# untitled.net
KiCad netlist of a schematic drawn in EAGLE
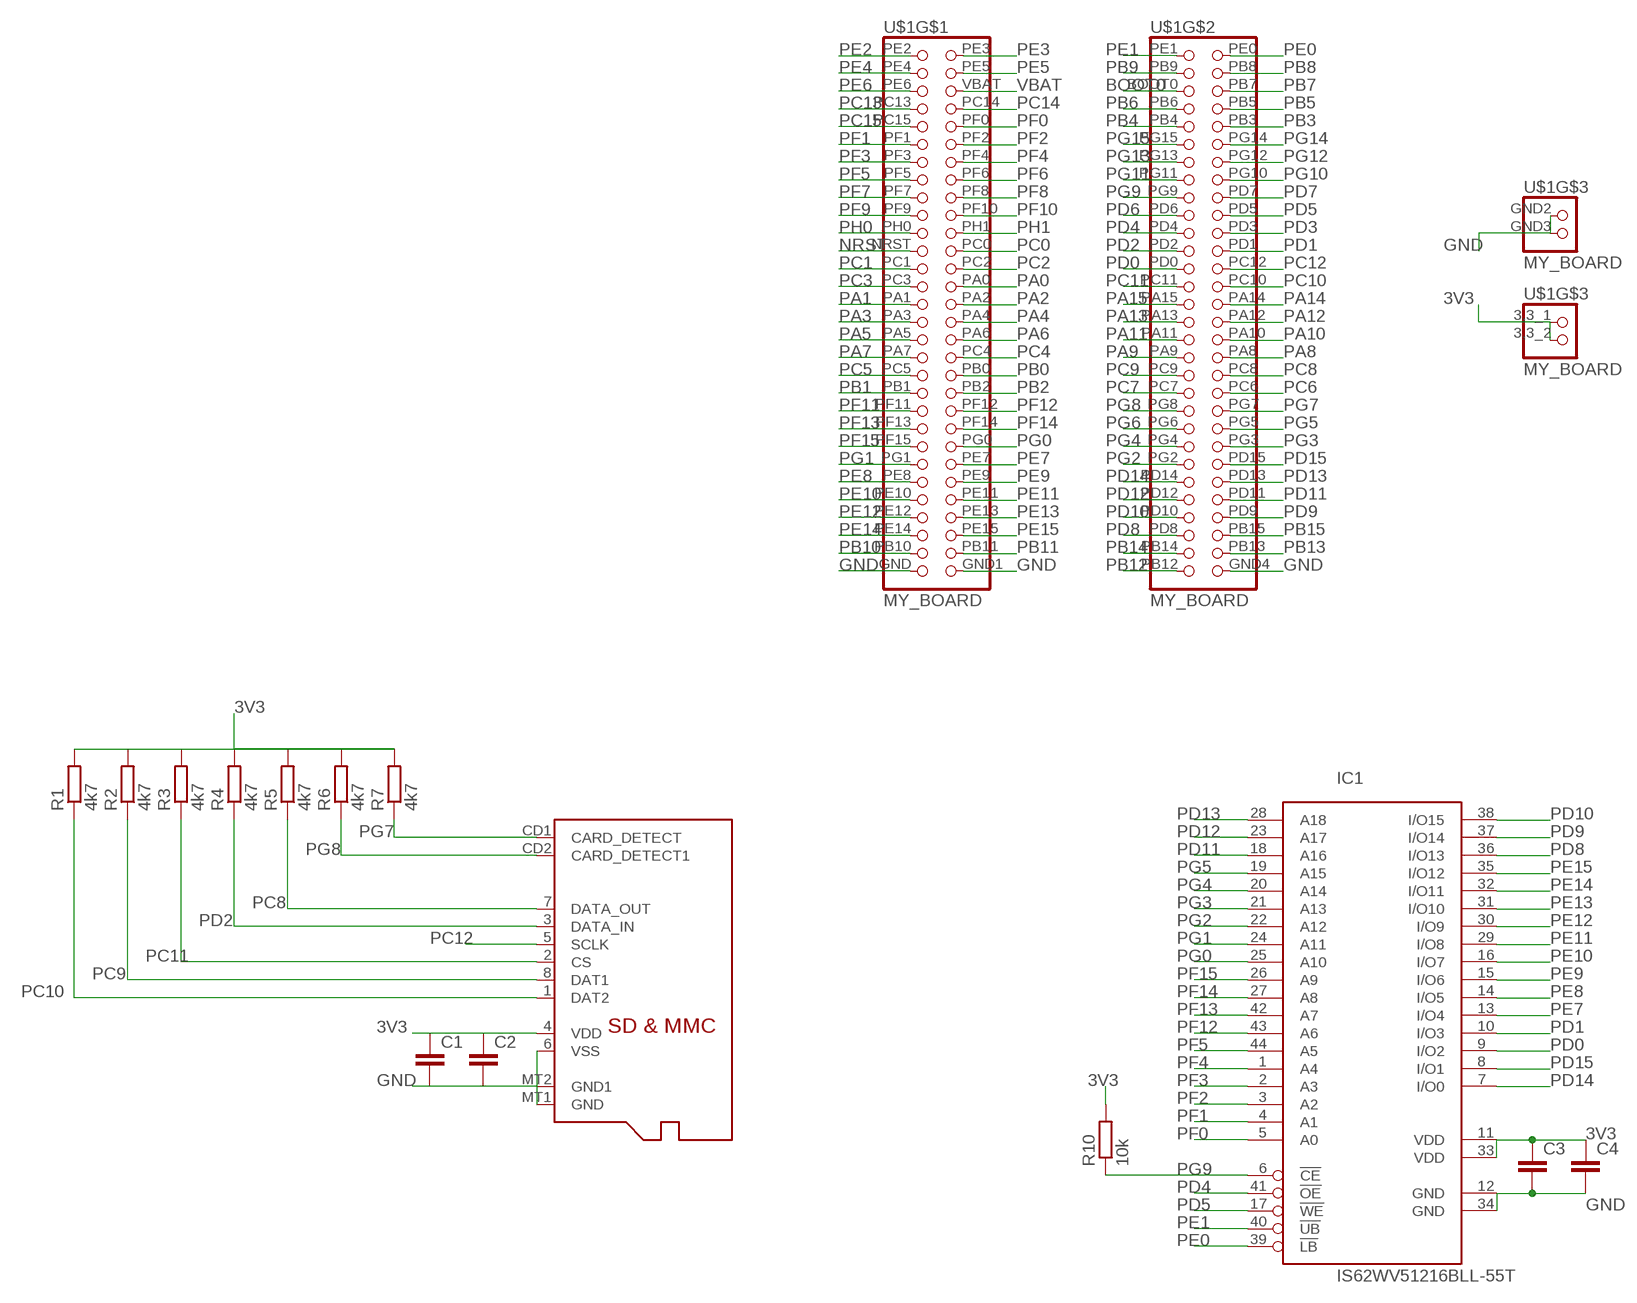
[diagram p0: schematic, sheet 1]

(export (version "E")
  (design (tool "Eeschema 10.0.6"))
  (components
    (comp (ref "C1")
      (value "C-EUC1206")
      (footprint "eagle-import:C1206")
      (libsource (lib "eagle-import") (part "C-EUC1206"))
    )
    (comp (ref "C2")
      (value "C-EUC1206")
      (footprint "eagle-import:C1206")
      (libsource (lib "eagle-import") (part "C-EUC1206"))
    )
    (comp (ref "C3")
      (value "C-EUC1206")
      (footprint "eagle-import:C1206")
      (libsource (lib "eagle-import") (part "C-EUC1206"))
    )
    (comp (ref "C4")
      (value "C-EUC1206")
      (footprint "eagle-import:C1206")
      (libsource (lib "eagle-import") (part "C-EUC1206"))
    )
    (comp (ref "IC1")
      (value "IS62WV51216BLL-55T")
      (footprint "eagle-import:TSOP-II-44")
      (libsource (lib "eagle-import") (part "IS62WV51216BLL-T55"))
    )
    (comp (ref "R1")
      (value "4k7")
      (footprint "eagle-import:R1206")
      (libsource (lib "eagle-import") (part "R-EU_R1206"))
    )
    (comp (ref "R2")
      (value "4k7")
      (footprint "eagle-import:R1206")
      (libsource (lib "eagle-import") (part "R-EU_R1206"))
    )
    (comp (ref "R3")
      (value "4k7")
      (footprint "eagle-import:R1206")
      (libsource (lib "eagle-import") (part "R-EU_R1206"))
    )
    (comp (ref "R4")
      (value "4k7")
      (footprint "eagle-import:R1206")
      (libsource (lib "eagle-import") (part "R-EU_R1206"))
    )
    (comp (ref "R5")
      (value "4k7")
      (footprint "eagle-import:R1206")
      (libsource (lib "eagle-import") (part "R-EU_R1206"))
    )
    (comp (ref "R6")
      (value "4k7")
      (footprint "eagle-import:R1206")
      (libsource (lib "eagle-import") (part "R-EU_R1206"))
    )
    (comp (ref "R7")
      (value "4k7")
      (footprint "eagle-import:R1206")
      (libsource (lib "eagle-import") (part "R-EU_R1206"))
    )
    (comp (ref "R10")
      (value "10k")
      (footprint "eagle-import:R1206")
      (libsource (lib "eagle-import") (part "R-EU_R1206"))
    )
    (comp (ref "U$1")
      (value "MY_BOARD")
      (footprint "eagle-import:MY_BOARD")
      (libsource (lib "eagle-import") (part "MY_BOARD"))
    )
    (comp (ref "U$5")
      (value "MICROSD")
      (footprint "eagle-import:MICROSD")
      (libsource (lib "eagle-import") (part "MICROSD"))
    )
  )
  (nets
    (net (code "1") (name "/3V3") (class "Default")
      (node (ref "C1") (pin "1") (pinfunction "1_1") (pintype "passive"))
      (node (ref "C2") (pin "1") (pinfunction "1_1") (pintype "passive"))
      (node (ref "C3") (pin "1") (pinfunction "1_1") (pintype "passive"))
      (node (ref "C4") (pin "1") (pinfunction "1_1") (pintype "passive"))
      (node (ref "IC1") (pin "11") (pinfunction "VDD_11") (pintype "power_in"))
      (node (ref "IC1") (pin "33") (pinfunction "VDD_33") (pintype "power_in"))
      (node (ref "R1") (pin "2") (pinfunction "2_2") (pintype "passive"))
      (node (ref "R10") (pin "2") (pinfunction "2_2") (pintype "passive"))
      (node (ref "R2") (pin "2") (pinfunction "2_2") (pintype "passive"))
      (node (ref "R3") (pin "2") (pinfunction "2_2") (pintype "passive"))
      (node (ref "R4") (pin "2") (pinfunction "2_2") (pintype "passive"))
      (node (ref "R5") (pin "2") (pinfunction "2_2") (pintype "passive"))
      (node (ref "R6") (pin "2") (pinfunction "2_2") (pintype "passive"))
      (node (ref "R7") (pin "2") (pinfunction "2_2") (pintype "passive"))
      (node (ref "U$1") (pin "3,3_1") (pinfunction "1_3,3_1") (pintype "passive"))
      (node (ref "U$1") (pin "3,3_2") (pinfunction "2_3,3_2") (pintype "passive"))
      (node (ref "U$5") (pin "4") (pinfunction "VDD_4") (pintype "power_in"))
    )
    (net (code "2") (name "/BOOT0") (class "Default")
      (node (ref "U$1") (pin "BOOT0") (pinfunction "5_BOOT0") (pintype "passive"))
    )
    (net (code "3") (name "/GND") (class "Default")
      (node (ref "C1") (pin "2") (pinfunction "2_2") (pintype "passive"))
      (node (ref "C2") (pin "2") (pinfunction "2_2") (pintype "passive"))
      (node (ref "C3") (pin "2") (pinfunction "2_2") (pintype "passive"))
      (node (ref "C4") (pin "2") (pinfunction "2_2") (pintype "passive"))
      (node (ref "IC1") (pin "12") (pinfunction "GND_12") (pintype "power_in"))
      (node (ref "IC1") (pin "34") (pinfunction "GND_34") (pintype "power_in"))
      (node (ref "U$1") (pin "GND") (pinfunction "59_GND") (pintype "passive"))
      (node (ref "U$1") (pin "GND1") (pinfunction "60_GND1") (pintype "passive"))
      (node (ref "U$1") (pin "GND2") (pinfunction "3_GND2") (pintype "passive"))
      (node (ref "U$1") (pin "GND3") (pinfunction "4_GND3") (pintype "passive"))
      (node (ref "U$1") (pin "GND4") (pinfunction "60_GND4") (pintype "passive"))
      (node (ref "U$5") (pin "6") (pinfunction "VSS_6") (pintype "power_in"))
      (node (ref "U$5") (pin "MT1") (pinfunction "GND_MT1") (pintype "power_in"))
      (node (ref "U$5") (pin "MT2") (pinfunction "GND1_MT2") (pintype "power_in"))
    )
    (net (code "4") (name "/NRST") (class "Default")
      (node (ref "U$1") (pin "NRST") (pinfunction "23_NRST") (pintype "passive"))
    )
    (net (code "5") (name "/PA0") (class "Default")
      (node (ref "U$1") (pin "PA0") (pinfunction "28_PA0") (pintype "passive"))
    )
    (net (code "6") (name "/PA1") (class "Default")
      (node (ref "U$1") (pin "PA1") (pinfunction "29_PA1") (pintype "passive"))
    )
    (net (code "7") (name "/PA2") (class "Default")
      (node (ref "U$1") (pin "PA2") (pinfunction "30_PA2") (pintype "passive"))
    )
    (net (code "8") (name "/PA3") (class "Default")
      (node (ref "U$1") (pin "PA3") (pinfunction "31_PA3") (pintype "passive"))
    )
    (net (code "9") (name "/PA4") (class "Default")
      (node (ref "U$1") (pin "PA4") (pinfunction "32_PA4") (pintype "passive"))
    )
    (net (code "10") (name "/PA5") (class "Default")
      (node (ref "U$1") (pin "PA5") (pinfunction "33_PA5") (pintype "passive"))
    )
    (net (code "11") (name "/PA6") (class "Default")
      (node (ref "U$1") (pin "PA6") (pinfunction "34_PA6") (pintype "passive"))
    )
    (net (code "12") (name "/PA7") (class "Default")
      (node (ref "U$1") (pin "PA7") (pinfunction "35_PA7") (pintype "passive"))
    )
    (net (code "13") (name "/PA8") (class "Default")
      (node (ref "U$1") (pin "PA8") (pinfunction "36_PA8") (pintype "passive"))
    )
    (net (code "14") (name "/PA9") (class "Default")
      (node (ref "U$1") (pin "PA9") (pinfunction "35_PA9") (pintype "passive"))
    )
    (net (code "15") (name "/PA10") (class "Default")
      (node (ref "U$1") (pin "PA10") (pinfunction "34_PA10") (pintype "passive"))
    )
    (net (code "16") (name "/PA11") (class "Default")
      (node (ref "U$1") (pin "PA11") (pinfunction "33_PA11") (pintype "passive"))
    )
    (net (code "17") (name "/PA12") (class "Default")
      (node (ref "U$1") (pin "PA12") (pinfunction "32_PA12") (pintype "passive"))
    )
    (net (code "18") (name "/PA13") (class "Default")
      (node (ref "U$1") (pin "PA13") (pinfunction "31_PA13") (pintype "passive"))
    )
    (net (code "19") (name "/PA14") (class "Default")
      (node (ref "U$1") (pin "PA14") (pinfunction "30_PA14") (pintype "passive"))
    )
    (net (code "20") (name "/PA15") (class "Default")
      (node (ref "U$1") (pin "PA15") (pinfunction "29_PA15") (pintype "passive"))
    )
    (net (code "21") (name "/PB0") (class "Default")
      (node (ref "U$1") (pin "PB0") (pinfunction "38_PB0") (pintype "passive"))
    )
    (net (code "22") (name "/PB1") (class "Default")
      (node (ref "U$1") (pin "PB1") (pinfunction "39_PB1") (pintype "passive"))
    )
    (net (code "23") (name "/PB2") (class "Default")
      (node (ref "U$1") (pin "PB2") (pinfunction "40_PB2") (pintype "passive"))
    )
    (net (code "24") (name "/PB3") (class "Default")
      (node (ref "U$1") (pin "PB3") (pinfunction "10_PB3") (pintype "passive"))
    )
    (net (code "25") (name "/PB4") (class "Default")
      (node (ref "U$1") (pin "PB4") (pinfunction "9_PB4") (pintype "passive"))
    )
    (net (code "26") (name "/PB5") (class "Default")
      (node (ref "U$1") (pin "PB5") (pinfunction "8_PB5") (pintype "passive"))
    )
    (net (code "27") (name "/PB6") (class "Default")
      (node (ref "U$1") (pin "PB6") (pinfunction "7_PB6") (pintype "passive"))
    )
    (net (code "28") (name "/PB7") (class "Default")
      (node (ref "U$1") (pin "PB7") (pinfunction "6_PB7") (pintype "passive"))
    )
    (net (code "29") (name "/PB8") (class "Default")
      (node (ref "U$1") (pin "PB8") (pinfunction "4_PB8") (pintype "passive"))
    )
    (net (code "30") (name "/PB9") (class "Default")
      (node (ref "U$1") (pin "PB9") (pinfunction "3_PB9") (pintype "passive"))
    )
    (net (code "31") (name "/PB10") (class "Default")
      (node (ref "U$1") (pin "PB10") (pinfunction "57_PB10") (pintype "passive"))
    )
    (net (code "32") (name "/PB11") (class "Default")
      (node (ref "U$1") (pin "PB11") (pinfunction "58_PB11") (pintype "passive"))
    )
    (net (code "33") (name "/PB12") (class "Default")
      (node (ref "U$1") (pin "PB12") (pinfunction "59_PB12") (pintype "passive"))
    )
    (net (code "34") (name "/PB13") (class "Default")
      (node (ref "U$1") (pin "PB13") (pinfunction "58_PB13") (pintype "passive"))
    )
    (net (code "35") (name "/PB14") (class "Default")
      (node (ref "U$1") (pin "PB14") (pinfunction "57_PB14") (pintype "passive"))
    )
    (net (code "36") (name "/PB15") (class "Default")
      (node (ref "U$1") (pin "PB15") (pinfunction "56_PB15") (pintype "passive"))
    )
    (net (code "37") (name "/PC0") (class "Default")
      (node (ref "U$1") (pin "PC0") (pinfunction "24_PC0") (pintype "passive"))
    )
    (net (code "38") (name "/PC1") (class "Default")
      (node (ref "U$1") (pin "PC1") (pinfunction "25_PC1") (pintype "passive"))
    )
    (net (code "39") (name "/PC2") (class "Default")
      (node (ref "U$1") (pin "PC2") (pinfunction "26_PC2") (pintype "passive"))
    )
    (net (code "40") (name "/PC3") (class "Default")
      (node (ref "U$1") (pin "PC3") (pinfunction "27_PC3") (pintype "passive"))
    )
    (net (code "41") (name "/PC4") (class "Default")
      (node (ref "U$1") (pin "PC4") (pinfunction "36_PC4") (pintype "passive"))
    )
    (net (code "42") (name "/PC5") (class "Default")
      (node (ref "U$1") (pin "PC5") (pinfunction "37_PC5") (pintype "passive"))
    )
    (net (code "43") (name "/PC6") (class "Default")
      (node (ref "U$1") (pin "PC6") (pinfunction "40_PC6") (pintype "passive"))
    )
    (net (code "44") (name "/PC7") (class "Default")
      (node (ref "U$1") (pin "PC7") (pinfunction "39_PC7") (pintype "passive"))
    )
    (net (code "45") (name "/PC8") (class "Default")
      (node (ref "R5") (pin "1") (pinfunction "1_1") (pintype "passive"))
      (node (ref "U$1") (pin "PC8") (pinfunction "38_PC8") (pintype "passive"))
      (node (ref "U$5") (pin "7") (pinfunction "DATA_OUT_7") (pintype "output"))
    )
    (net (code "46") (name "/PC9") (class "Default")
      (node (ref "R2") (pin "1") (pinfunction "1_1") (pintype "passive"))
      (node (ref "U$1") (pin "PC9") (pinfunction "37_PC9") (pintype "passive"))
      (node (ref "U$5") (pin "8") (pinfunction "DAT1_8") (pintype "bidirectional"))
    )
    (net (code "47") (name "/PC10") (class "Default")
      (node (ref "R1") (pin "1") (pinfunction "1_1") (pintype "passive"))
      (node (ref "U$1") (pin "PC10") (pinfunction "28_PC10") (pintype "passive"))
      (node (ref "U$5") (pin "1") (pinfunction "DAT2_1") (pintype "bidirectional"))
    )
    (net (code "48") (name "/PC11") (class "Default")
      (node (ref "R3") (pin "1") (pinfunction "1_1") (pintype "passive"))
      (node (ref "U$1") (pin "PC11") (pinfunction "27_PC11") (pintype "passive"))
      (node (ref "U$5") (pin "2") (pinfunction "CS_2") (pintype "input"))
    )
    (net (code "49") (name "/PC12") (class "Default")
      (node (ref "U$1") (pin "PC12") (pinfunction "26_PC12") (pintype "passive"))
      (node (ref "U$5") (pin "5") (pinfunction "SCLK_5") (pintype "input"))
    )
    (net (code "50") (name "/PC13") (class "Default")
      (node (ref "U$1") (pin "PC13") (pinfunction "7_PC13") (pintype "passive"))
    )
    (net (code "51") (name "/PC14") (class "Default")
      (node (ref "U$1") (pin "PC14") (pinfunction "8_PC14") (pintype "passive"))
    )
    (net (code "52") (name "/PC15") (class "Default")
      (node (ref "U$1") (pin "PC15") (pinfunction "9_PC15") (pintype "passive"))
    )
    (net (code "53") (name "/PD0") (class "Default")
      (node (ref "IC1") (pin "9") (pinfunction "I/O2_9") (pintype "tri_state"))
      (node (ref "U$1") (pin "PD0") (pinfunction "25_PD0") (pintype "passive"))
    )
    (net (code "54") (name "/PD1") (class "Default")
      (node (ref "IC1") (pin "10") (pinfunction "I/O3_10") (pintype "tri_state"))
      (node (ref "U$1") (pin "PD1") (pinfunction "24_PD1") (pintype "passive"))
    )
    (net (code "55") (name "/PD2") (class "Default")
      (node (ref "R4") (pin "1") (pinfunction "1_1") (pintype "passive"))
      (node (ref "U$1") (pin "PD2") (pinfunction "23_PD2") (pintype "passive"))
      (node (ref "U$5") (pin "3") (pinfunction "DATA_IN_3") (pintype "input"))
    )
    (net (code "56") (name "/PD3") (class "Default")
      (node (ref "U$1") (pin "PD3") (pinfunction "22_PD3") (pintype "passive"))
    )
    (net (code "57") (name "/PD4") (class "Default")
      (node (ref "IC1") (pin "41") (pinfunction "~{OE}_41") (pintype "input"))
      (node (ref "U$1") (pin "PD4") (pinfunction "21_PD4") (pintype "passive"))
    )
    (net (code "58") (name "/PD5") (class "Default")
      (node (ref "IC1") (pin "17") (pinfunction "~{WE}_17") (pintype "input"))
      (node (ref "U$1") (pin "PD5") (pinfunction "20_PD5") (pintype "passive"))
    )
    (net (code "59") (name "/PD6") (class "Default")
      (node (ref "U$1") (pin "PD6") (pinfunction "19_PD6") (pintype "passive"))
    )
    (net (code "60") (name "/PD7") (class "Default")
      (node (ref "U$1") (pin "PD7") (pinfunction "18_PD7") (pintype "passive"))
    )
    (net (code "61") (name "/PD8") (class "Default")
      (node (ref "IC1") (pin "36") (pinfunction "I/O13_36") (pintype "tri_state"))
      (node (ref "U$1") (pin "PD8") (pinfunction "55_PD8") (pintype "passive"))
    )
    (net (code "62") (name "/PD9") (class "Default")
      (node (ref "IC1") (pin "37") (pinfunction "I/O14_37") (pintype "tri_state"))
      (node (ref "U$1") (pin "PD9") (pinfunction "54_PD9") (pintype "passive"))
    )
    (net (code "63") (name "/PD10") (class "Default")
      (node (ref "IC1") (pin "38") (pinfunction "I/O15_38") (pintype "tri_state"))
      (node (ref "U$1") (pin "PD10") (pinfunction "53_PD10") (pintype "passive"))
    )
    (net (code "64") (name "/PD11") (class "Default")
      (node (ref "IC1") (pin "18") (pinfunction "A16_18") (pintype "input"))
      (node (ref "U$1") (pin "PD11") (pinfunction "52_PD11") (pintype "passive"))
    )
    (net (code "65") (name "/PD12") (class "Default")
      (node (ref "IC1") (pin "23") (pinfunction "A17_23") (pintype "input"))
      (node (ref "U$1") (pin "PD12") (pinfunction "51_PD12") (pintype "passive"))
    )
    (net (code "66") (name "/PD13") (class "Default")
      (node (ref "IC1") (pin "28") (pinfunction "A18_28") (pintype "input"))
      (node (ref "U$1") (pin "PD13") (pinfunction "50_PD13") (pintype "passive"))
    )
    (net (code "67") (name "/PD14") (class "Default")
      (node (ref "IC1") (pin "7") (pinfunction "I/O0_7") (pintype "tri_state"))
      (node (ref "U$1") (pin "PD14") (pinfunction "49_PD14") (pintype "passive"))
    )
    (net (code "68") (name "/PD15") (class "Default")
      (node (ref "IC1") (pin "8") (pinfunction "I/O1_8") (pintype "tri_state"))
      (node (ref "U$1") (pin "PD15") (pinfunction "48_PD15") (pintype "passive"))
    )
    (net (code "69") (name "/PE0") (class "Default")
      (node (ref "IC1") (pin "39") (pinfunction "~{LB}_39") (pintype "input"))
      (node (ref "U$1") (pin "PE0") (pinfunction "2_PE0") (pintype "passive"))
    )
    (net (code "70") (name "/PE1") (class "Default")
      (node (ref "IC1") (pin "40") (pinfunction "~{UB}_40") (pintype "input"))
      (node (ref "U$1") (pin "PE1") (pinfunction "1_PE1") (pintype "passive"))
    )
    (net (code "71") (name "/PE2") (class "Default")
      (node (ref "U$1") (pin "PE2") (pinfunction "1_PE2") (pintype "passive"))
    )
    (net (code "72") (name "/PE3") (class "Default")
      (node (ref "U$1") (pin "PE3") (pinfunction "2_PE3") (pintype "passive"))
    )
    (net (code "73") (name "/PE4") (class "Default")
      (node (ref "U$1") (pin "PE4") (pinfunction "3_PE4") (pintype "passive"))
    )
    (net (code "74") (name "/PE5") (class "Default")
      (node (ref "U$1") (pin "PE5") (pinfunction "4_PE5") (pintype "passive"))
    )
    (net (code "75") (name "/PE6") (class "Default")
      (node (ref "U$1") (pin "PE6") (pinfunction "5_PE6") (pintype "passive"))
    )
    (net (code "76") (name "/PE7") (class "Default")
      (node (ref "IC1") (pin "13") (pinfunction "I/O4_13") (pintype "tri_state"))
      (node (ref "U$1") (pin "PE7") (pinfunction "48_PE7") (pintype "passive"))
    )
    (net (code "77") (name "/PE8") (class "Default")
      (node (ref "IC1") (pin "14") (pinfunction "I/O5_14") (pintype "tri_state"))
      (node (ref "U$1") (pin "PE8") (pinfunction "49_PE8") (pintype "passive"))
    )
    (net (code "78") (name "/PE9") (class "Default")
      (node (ref "IC1") (pin "15") (pinfunction "I/O6_15") (pintype "tri_state"))
      (node (ref "U$1") (pin "PE9") (pinfunction "50_PE9") (pintype "passive"))
    )
    (net (code "79") (name "/PE10") (class "Default")
      (node (ref "IC1") (pin "16") (pinfunction "I/O7_16") (pintype "tri_state"))
      (node (ref "U$1") (pin "PE10") (pinfunction "51_PE10") (pintype "passive"))
    )
    (net (code "80") (name "/PE11") (class "Default")
      (node (ref "IC1") (pin "29") (pinfunction "I/O8_29") (pintype "tri_state"))
      (node (ref "U$1") (pin "PE11") (pinfunction "52_PE11") (pintype "passive"))
    )
    (net (code "81") (name "/PE12") (class "Default")
      (node (ref "IC1") (pin "30") (pinfunction "I/O9_30") (pintype "tri_state"))
      (node (ref "U$1") (pin "PE12") (pinfunction "53_PE12") (pintype "passive"))
    )
    (net (code "82") (name "/PE13") (class "Default")
      (node (ref "IC1") (pin "31") (pinfunction "I/O10_31") (pintype "tri_state"))
      (node (ref "U$1") (pin "PE13") (pinfunction "54_PE13") (pintype "passive"))
    )
    (net (code "83") (name "/PE14") (class "Default")
      (node (ref "IC1") (pin "32") (pinfunction "I/O11_32") (pintype "tri_state"))
      (node (ref "U$1") (pin "PE14") (pinfunction "55_PE14") (pintype "passive"))
    )
    (net (code "84") (name "/PE15") (class "Default")
      (node (ref "IC1") (pin "35") (pinfunction "I/O12_35") (pintype "tri_state"))
      (node (ref "U$1") (pin "PE15") (pinfunction "56_PE15") (pintype "passive"))
    )
    (net (code "85") (name "/PF0") (class "Default")
      (node (ref "IC1") (pin "5") (pinfunction "A0_5") (pintype "input"))
      (node (ref "U$1") (pin "PF0") (pinfunction "10_PF0") (pintype "passive"))
    )
    (net (code "86") (name "/PF1") (class "Default")
      (node (ref "IC1") (pin "4") (pinfunction "A1_4") (pintype "input"))
      (node (ref "U$1") (pin "PF1") (pinfunction "11_PF1") (pintype "passive"))
    )
    (net (code "87") (name "/PF2") (class "Default")
      (node (ref "IC1") (pin "3") (pinfunction "A2_3") (pintype "input"))
      (node (ref "U$1") (pin "PF2") (pinfunction "12_PF2") (pintype "passive"))
    )
    (net (code "88") (name "/PF3") (class "Default")
      (node (ref "IC1") (pin "2") (pinfunction "A3_2") (pintype "input"))
      (node (ref "U$1") (pin "PF3") (pinfunction "13_PF3") (pintype "passive"))
    )
    (net (code "89") (name "/PF4") (class "Default")
      (node (ref "IC1") (pin "1") (pinfunction "A4_1") (pintype "input"))
      (node (ref "U$1") (pin "PF4") (pinfunction "14_PF4") (pintype "passive"))
    )
    (net (code "90") (name "/PF5") (class "Default")
      (node (ref "IC1") (pin "44") (pinfunction "A5_44") (pintype "input"))
      (node (ref "U$1") (pin "PF5") (pinfunction "15_PF5") (pintype "passive"))
    )
    (net (code "91") (name "/PF6") (class "Default")
      (node (ref "U$1") (pin "PF6") (pinfunction "16_PF6") (pintype "passive"))
    )
    (net (code "92") (name "/PF7") (class "Default")
      (node (ref "U$1") (pin "PF7") (pinfunction "17_PF7") (pintype "passive"))
    )
    (net (code "93") (name "/PF8") (class "Default")
      (node (ref "U$1") (pin "PF8") (pinfunction "18_PF8") (pintype "passive"))
    )
    (net (code "94") (name "/PF9") (class "Default")
      (node (ref "U$1") (pin "PF9") (pinfunction "19_PF9") (pintype "passive"))
    )
    (net (code "95") (name "/PF10") (class "Default")
      (node (ref "U$1") (pin "PF10") (pinfunction "20_PF10") (pintype "passive"))
    )
    (net (code "96") (name "/PF11") (class "Default")
      (node (ref "U$1") (pin "PF11") (pinfunction "41_PF11") (pintype "passive"))
    )
    (net (code "97") (name "/PF12") (class "Default")
      (node (ref "IC1") (pin "43") (pinfunction "A6_43") (pintype "input"))
      (node (ref "U$1") (pin "PF12") (pinfunction "42_PF12") (pintype "passive"))
    )
    (net (code "98") (name "/PF13") (class "Default")
      (node (ref "IC1") (pin "42") (pinfunction "A7_42") (pintype "input"))
      (node (ref "U$1") (pin "PF13") (pinfunction "43_PF13") (pintype "passive"))
    )
    (net (code "99") (name "/PF14") (class "Default")
      (node (ref "IC1") (pin "27") (pinfunction "A8_27") (pintype "input"))
      (node (ref "U$1") (pin "PF14") (pinfunction "44_PF14") (pintype "passive"))
    )
    (net (code "100") (name "/PF15") (class "Default")
      (node (ref "IC1") (pin "26") (pinfunction "A9_26") (pintype "input"))
      (node (ref "U$1") (pin "PF15") (pinfunction "45_PF15") (pintype "passive"))
    )
    (net (code "101") (name "/PG0") (class "Default")
      (node (ref "IC1") (pin "25") (pinfunction "A10_25") (pintype "input"))
      (node (ref "U$1") (pin "PG0") (pinfunction "46_PG0") (pintype "passive"))
    )
    (net (code "102") (name "/PG1") (class "Default")
      (node (ref "IC1") (pin "24") (pinfunction "A11_24") (pintype "input"))
      (node (ref "U$1") (pin "PG1") (pinfunction "47_PG1") (pintype "passive"))
    )
    (net (code "103") (name "/PG2") (class "Default")
      (node (ref "IC1") (pin "22") (pinfunction "A12_22") (pintype "input"))
      (node (ref "U$1") (pin "PG2") (pinfunction "47_PG2") (pintype "passive"))
    )
    (net (code "104") (name "/PG3") (class "Default")
      (node (ref "IC1") (pin "21") (pinfunction "A13_21") (pintype "input"))
      (node (ref "U$1") (pin "PG3") (pinfunction "46_PG3") (pintype "passive"))
    )
    (net (code "105") (name "/PG4") (class "Default")
      (node (ref "IC1") (pin "20") (pinfunction "A14_20") (pintype "input"))
      (node (ref "U$1") (pin "PG4") (pinfunction "45_PG4") (pintype "passive"))
    )
    (net (code "106") (name "/PG5") (class "Default")
      (node (ref "IC1") (pin "19") (pinfunction "A15_19") (pintype "input"))
      (node (ref "U$1") (pin "PG5") (pinfunction "44_PG5") (pintype "passive"))
    )
    (net (code "107") (name "/PG6") (class "Default")
      (node (ref "U$1") (pin "PG6") (pinfunction "43_PG6") (pintype "passive"))
    )
    (net (code "108") (name "/PG7") (class "Default")
      (node (ref "R7") (pin "1") (pinfunction "1_1") (pintype "passive"))
      (node (ref "U$1") (pin "PG7") (pinfunction "42_PG7") (pintype "passive"))
      (node (ref "U$5") (pin "CD1") (pinfunction "CARD_DETECT_CD1") (pintype "passive"))
    )
    (net (code "109") (name "/PG8") (class "Default")
      (node (ref "R6") (pin "1") (pinfunction "1_1") (pintype "passive"))
      (node (ref "U$1") (pin "PG8") (pinfunction "41_PG8") (pintype "passive"))
      (node (ref "U$5") (pin "CD2") (pinfunction "CARD_DETECT1_CD2") (pintype "passive"))
    )
    (net (code "110") (name "/PG9") (class "Default")
      (node (ref "IC1") (pin "6") (pinfunction "~{CE}_6") (pintype "input"))
      (node (ref "R10") (pin "1") (pinfunction "1_1") (pintype "passive"))
      (node (ref "U$1") (pin "PG9") (pinfunction "17_PG9") (pintype "passive"))
    )
    (net (code "111") (name "/PG10") (class "Default")
      (node (ref "U$1") (pin "PG10") (pinfunction "16_PG10") (pintype "passive"))
    )
    (net (code "112") (name "/PG11") (class "Default")
      (node (ref "U$1") (pin "PG11") (pinfunction "15_PG11") (pintype "passive"))
    )
    (net (code "113") (name "/PG12") (class "Default")
      (node (ref "U$1") (pin "PG12") (pinfunction "14_PG12") (pintype "passive"))
    )
    (net (code "114") (name "/PG13") (class "Default")
      (node (ref "U$1") (pin "PG13") (pinfunction "13_PG13") (pintype "passive"))
    )
    (net (code "115") (name "/PG14") (class "Default")
      (node (ref "U$1") (pin "PG14") (pinfunction "12_PG14") (pintype "passive"))
    )
    (net (code "116") (name "/PG15") (class "Default")
      (node (ref "U$1") (pin "PG15") (pinfunction "11_PG15") (pintype "passive"))
    )
    (net (code "117") (name "/PH0") (class "Default")
      (node (ref "U$1") (pin "PH0") (pinfunction "21_PH0") (pintype "passive"))
    )
    (net (code "118") (name "/PH1") (class "Default")
      (node (ref "U$1") (pin "PH1") (pinfunction "22_PH1") (pintype "passive"))
    )
    (net (code "119") (name "/VBAT") (class "Default")
      (node (ref "U$1") (pin "VBAT") (pinfunction "6_VBAT") (pintype "passive"))
    )
  )
)
